# InWallDimmeSMD.net
KiCad netlist of a schematic drawn in EAGLE
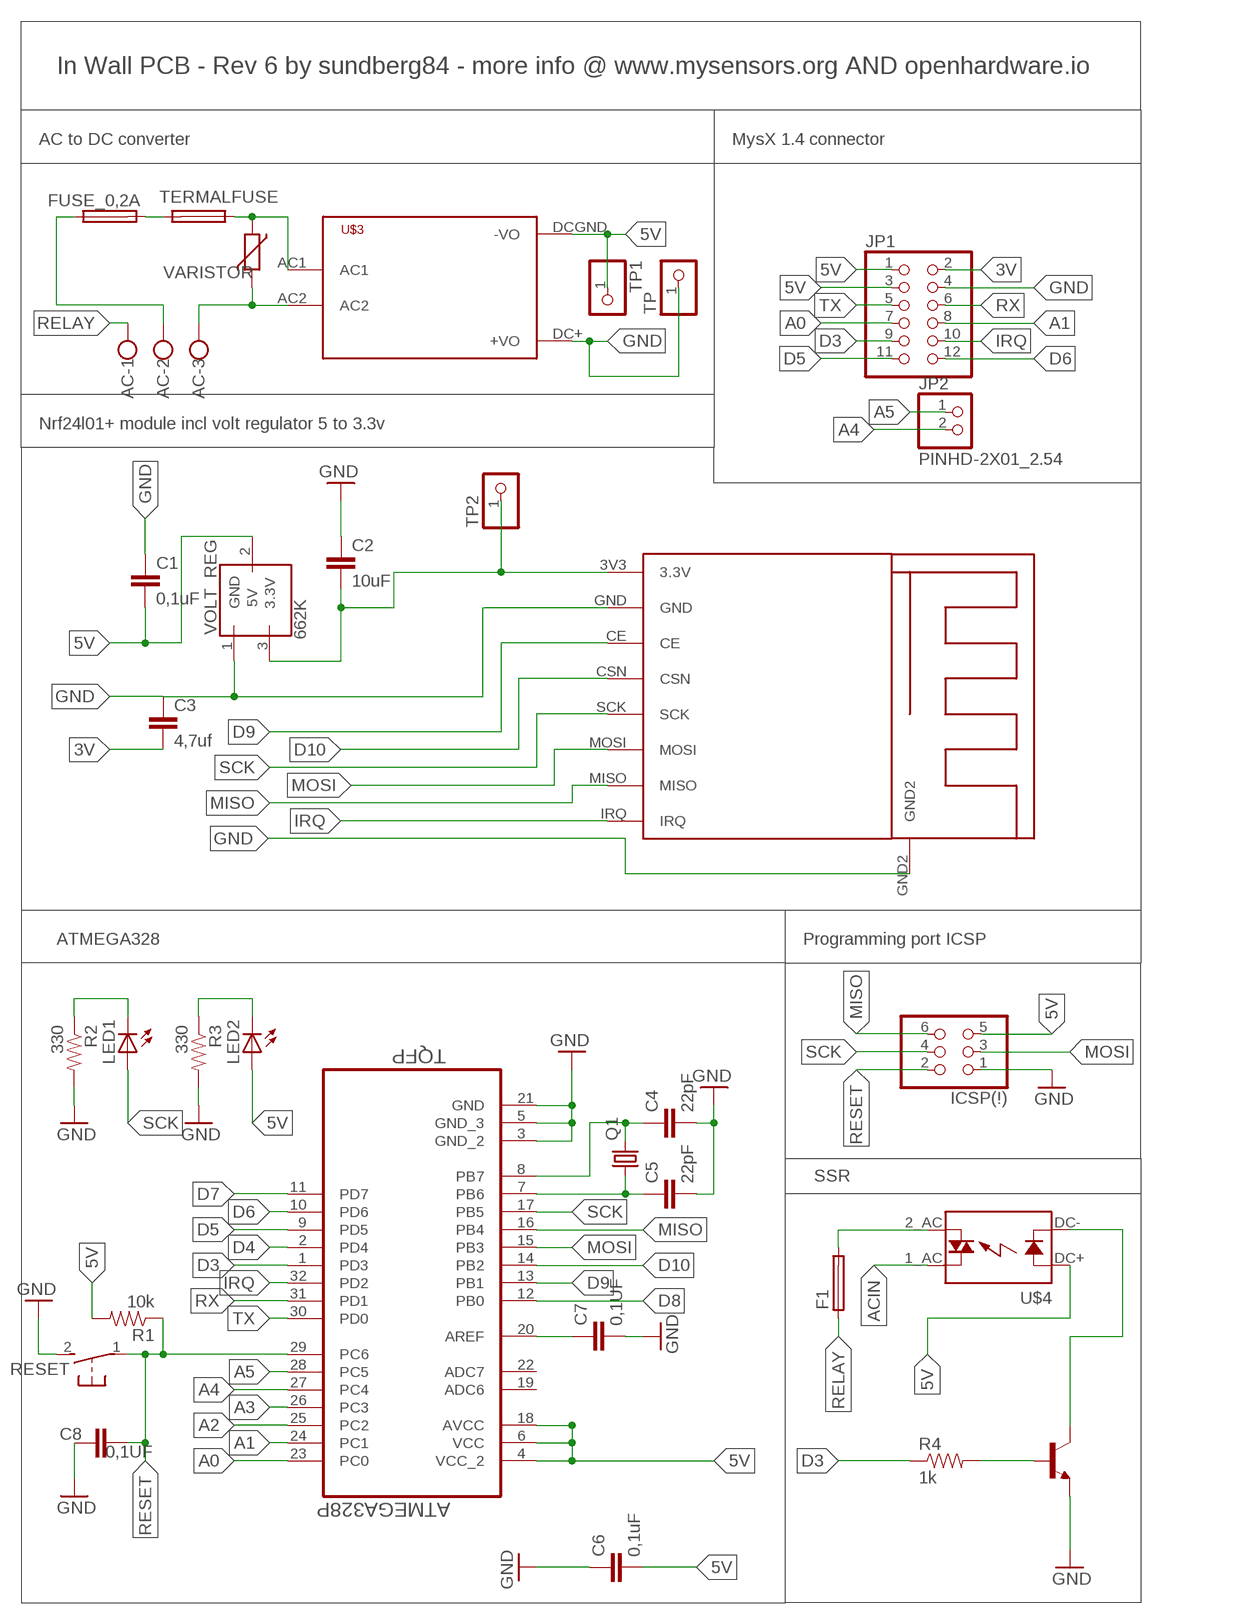
[diagram p0: schematic, sheet 1]

(export (version "E")
  (design (tool "Eeschema 10.0.6"))
  (components
    (comp (ref "AC")
      (value "W237-103")
      (footprint "eagle-import:W237-103")
      (fields (field (name "MPN") "237-103"))
      (libsource (lib "eagle-import") (part "W237-103"))
    )
    (comp (ref "ATMEGA328")
      (value "ATMEGA328P-AU")
      (footprint "eagle-import:QFP80P900X900X120-32N")
      (libsource (lib "eagle-import") (part "ATMEGA328P-AU"))
    )
    (comp (ref "C1")
      (value "0,1uF")
      (footprint "eagle-import:0805")
      (libsource (lib "eagle-import") (part "CAP0805"))
    )
    (comp (ref "C2")
      (value "10uF")
      (footprint "eagle-import:0805")
      (libsource (lib "eagle-import") (part "CAP0805"))
    )
    (comp (ref "C3")
      (value "4,7uf")
      (footprint "eagle-import:0805")
      (libsource (lib "eagle-import") (part "CAP0805"))
    )
    (comp (ref "C4")
      (value "22pF")
      (footprint "eagle-import:0805")
      (libsource (lib "eagle-import") (part "CAP0805"))
    )
    (comp (ref "C5")
      (value "22pF")
      (footprint "eagle-import:0805")
      (libsource (lib "eagle-import") (part "CAP0805"))
    )
    (comp (ref "C6")
      (value "0,1uF")
      (footprint "eagle-import:0805")
      (libsource (lib "eagle-import") (part "CAP0805"))
    )
    (comp (ref "C7")
      (value "0,1UF")
      (footprint "eagle-import:0805")
      (libsource (lib "eagle-import") (part "CAP0805"))
    )
    (comp (ref "C8")
      (value "0,1UF")
      (footprint "eagle-import:0805")
      (libsource (lib "eagle-import") (part "CAP0805"))
    )
    (comp (ref "F1")
      (value "19559")
      (footprint "eagle-import:19559")
      (fields (field (name "MPN") "55900000001"))
      (libsource (lib "eagle-import") (part "19559"))
    )
    (comp (ref "FUSE_0,2A")
      (value "FUSETE5")
      (footprint "eagle-import:TE5")
      (libsource (lib "eagle-import") (part "FUSETE5"))
    )
    (comp (ref "ICSP(!)")
      (value "PINHD-2X03_2.54")
      (footprint "eagle-import:2X03")
      (libsource (lib "eagle-import") (part "PINHD-2X03_2.54"))
    )
    (comp (ref "J3Y")
      (value "J3Y_S8050_SMD_NPN_TRANSISTOR")
      (footprint "eagle-import:SOT-23-3")
      (libsource (lib "eagle-import") (part "J3Y_S8050_SMD_NPN_TRANSISTOR"))
    )
    (comp (ref "JP1")
      (value "PINHD-2X06_2.54")
      (footprint "eagle-import:2X06")
      (libsource (lib "eagle-import") (part "PINHD-2X06_2.54"))
    )
    (comp (ref "JP2")
      (value "PINHD-2X01_2.54")
      (footprint "eagle-import:2X01")
      (libsource (lib "eagle-import") (part "PINHD-2X01_2.54"))
    )
    (comp (ref "LED1")
      (value "LEDCHIPLED_0805")
      (footprint "eagle-import:CHIPLED_0805")
      (libsource (lib "eagle-import") (part "LEDCHIPLED_0805"))
    )
    (comp (ref "LED2")
      (value "LEDCHIPLED_0805")
      (footprint "eagle-import:CHIPLED_0805")
      (libsource (lib "eagle-import") (part "LEDCHIPLED_0805"))
    )
    (comp (ref "Q1")
      (value "CRYSTALHC49S")
      (footprint "eagle-import:HC49_S")
      (libsource (lib "eagle-import") (part "CRYSTALHC49S"))
    )
    (comp (ref "R1")
      (value "10k")
      (footprint "eagle-import:0805")
      (libsource (lib "eagle-import") (part "RESISTOR0805-RES"))
    )
    (comp (ref "R2")
      (value "330")
      (footprint "eagle-import:0805")
      (libsource (lib "eagle-import") (part "RESISTOR0805-RES"))
    )
    (comp (ref "R3")
      (value "330")
      (footprint "eagle-import:0805")
      (libsource (lib "eagle-import") (part "RESISTOR0805-RES"))
    )
    (comp (ref "R4")
      (value "1k")
      (footprint "eagle-import:0805")
      (libsource (lib "eagle-import") (part "RESISTOR0805-RES"))
    )
    (comp (ref "RESET")
      (value "DTSM-3")
      (footprint "eagle-import:DTSM-3")
      (libsource (lib "eagle-import") (part "DTSM-3"))
    )
    (comp (ref "TERMALFUSE")
      (value "FUSETE5")
      (footprint "eagle-import:TE5")
      (libsource (lib "eagle-import") (part "FUSETE5"))
    )
    (comp (ref "TP")
      (value "PINHD-1X1")
      (footprint "eagle-import:1X01")
      (libsource (lib "eagle-import") (part "PINHD-1X1"))
    )
    (comp (ref "TP1")
      (value "PINHD-1X1")
      (footprint "eagle-import:1X01")
      (libsource (lib "eagle-import") (part "PINHD-1X1"))
    )
    (comp (ref "TP2")
      (value "PINHD-1X1")
      (footprint "eagle-import:1X01")
      (libsource (lib "eagle-import") (part "PINHD-1X1"))
    )
    (comp (ref "U$1")
      (value "SMD24L01+SMD")
      (footprint "eagle-import:NRF24L01+SMD")
      (libsource (lib "eagle-import") (part "SMD24L01+SMD"))
    )
    (comp (ref "U$3")
      (value "HLK-PM01")
      (footprint "eagle-import:HLK-PM01")
      (libsource (lib "eagle-import") (part "HLK-PM01"))
    )
    (comp (ref "U$4")
      (value "OMRON_G3MC-202PL_5V_SSR")
      (footprint "eagle-import:OMRON_G3MC_202PL_5V_SSR")
      (libsource (lib "eagle-import") (part "OMRON_G3MC-202PL_5V_SSR"))
    )
    (comp (ref "VARISTOR")
      (value "VARISTOR-7,5")
      (footprint "eagle-import:R-7,5")
      (libsource (lib "eagle-import") (part "VARISTOR-7,5"))
    )
    (comp (ref "VOLT_REG")
      (value "662K")
      (footprint "eagle-import:SOT-23-3")
      (libsource (lib "eagle-import") (part "662K"))
    )
  )
  (nets
    (net (code "1") (name "3V") (class "Default")
      (node (ref "C2") (pin "2") (pinfunction "2_2") (pintype "passive"))
      (node (ref "C3") (pin "2") (pinfunction "2_2") (pintype "passive"))
      (node (ref "JP1") (pin "2") (pinfunction "2_2") (pintype "passive"))
      (node (ref "TP2") (pin "1") (pinfunction "1_1") (pintype "passive"))
      (node (ref "U$1") (pin "3V3") (pinfunction "3.3V_3V3") (pintype "bidirectional"))
      (node (ref "VOLT_REG") (pin "3") (pinfunction "3.3V_3") (pintype "bidirectional"))
    )
    (net (code "2") (name "5V") (class "Default")
      (node (ref "ATMEGA328") (pin "18") (pinfunction "AVCC_18") (pintype "power_in"))
      (node (ref "ATMEGA328") (pin "4") (pinfunction "VCC_2_4") (pintype "power_in"))
      (node (ref "ATMEGA328") (pin "6") (pinfunction "VCC_6") (pintype "power_in"))
      (node (ref "C1") (pin "2") (pinfunction "2_2") (pintype "passive"))
      (node (ref "C6") (pin "2") (pinfunction "2_2") (pintype "passive"))
      (node (ref "ICSP(!)") (pin "5") (pinfunction "5_5") (pintype "passive"))
      (node (ref "JP1") (pin "1") (pinfunction "1_1") (pintype "passive"))
      (node (ref "JP1") (pin "3") (pinfunction "3_3") (pintype "passive"))
      (node (ref "LED2") (pin "A") (pinfunction "A_A") (pintype "passive"))
      (node (ref "R1") (pin "2") (pinfunction "2_2") (pintype "passive"))
      (node (ref "TP1") (pin "1") (pinfunction "1_1") (pintype "passive"))
      (node (ref "U$3") (pin "DCGND") (pinfunction "-VO_DCGND") (pintype "bidirectional"))
      (node (ref "U$4") (pin "DC+") (pinfunction "DCSIGNAL_DC+") (pintype "passive"))
      (node (ref "VOLT_REG") (pin "2") (pinfunction "5V_2") (pintype "bidirectional"))
    )
    (net (code "3") (name "A0") (class "Default")
      (node (ref "ATMEGA328") (pin "23") (pinfunction "PC0_23") (pintype "bidirectional"))
      (node (ref "JP1") (pin "7") (pinfunction "7_7") (pintype "passive"))
    )
    (net (code "4") (name "A1") (class "Default")
      (node (ref "ATMEGA328") (pin "24") (pinfunction "PC1_24") (pintype "bidirectional"))
      (node (ref "JP1") (pin "8") (pinfunction "8_8") (pintype "passive"))
    )
    (net (code "5") (name "A2") (class "Default")
      (node (ref "ATMEGA328") (pin "25") (pinfunction "PC2_25") (pintype "bidirectional"))
    )
    (net (code "6") (name "A3") (class "Default")
      (node (ref "ATMEGA328") (pin "26") (pinfunction "PC3_26") (pintype "bidirectional"))
    )
    (net (code "7") (name "A4") (class "Default")
      (node (ref "ATMEGA328") (pin "27") (pinfunction "PC4_27") (pintype "bidirectional"))
      (node (ref "JP2") (pin "2") (pinfunction "2_2") (pintype "passive"))
    )
    (net (code "8") (name "A5") (class "Default")
      (node (ref "ATMEGA328") (pin "28") (pinfunction "PC5_28") (pintype "bidirectional"))
      (node (ref "JP2") (pin "1") (pinfunction "1_1") (pintype "passive"))
    )
    (net (code "9") (name "ACIN") (class "Default")
      (node (ref "AC") (pin "2") (pinfunction "KL_2") (pintype "passive"))
      (node (ref "FUSE_0,2A") (pin "1") (pinfunction "1_1") (pintype "passive"))
      (node (ref "U$4") (pin "1_AC") (pinfunction "HOT_1_AC") (pintype "passive"))
    )
    (net (code "10") (name "D3") (class "Default")
      (node (ref "ATMEGA328") (pin "1") (pinfunction "PD3_1") (pintype "bidirectional"))
      (node (ref "JP1") (pin "9") (pinfunction "9_9") (pintype "passive"))
      (node (ref "R4") (pin "1") (pinfunction "1_1") (pintype "passive"))
    )
    (net (code "11") (name "D4") (class "Default")
      (node (ref "ATMEGA328") (pin "2") (pinfunction "PD4_2") (pintype "bidirectional"))
    )
    (net (code "12") (name "D5") (class "Default")
      (node (ref "ATMEGA328") (pin "9") (pinfunction "PD5_9") (pintype "bidirectional"))
      (node (ref "JP1") (pin "11") (pinfunction "11_11") (pintype "passive"))
    )
    (net (code "13") (name "D6") (class "Default")
      (node (ref "ATMEGA328") (pin "10") (pinfunction "PD6_10") (pintype "bidirectional"))
      (node (ref "JP1") (pin "12") (pinfunction "12_12") (pintype "passive"))
    )
    (net (code "14") (name "D7") (class "Default")
      (node (ref "ATMEGA328") (pin "11") (pinfunction "PD7_11") (pintype "bidirectional"))
    )
    (net (code "15") (name "D8") (class "Default")
      (node (ref "ATMEGA328") (pin "12") (pinfunction "PB0_12") (pintype "bidirectional"))
    )
    (net (code "16") (name "D9") (class "Default")
      (node (ref "ATMEGA328") (pin "13") (pinfunction "PB1_13") (pintype "bidirectional"))
      (node (ref "U$1") (pin "CE") (pinfunction "CE_CE") (pintype "bidirectional"))
    )
    (net (code "17") (name "D10") (class "Default")
      (node (ref "ATMEGA328") (pin "14") (pinfunction "PB2_14") (pintype "bidirectional"))
      (node (ref "U$1") (pin "CSN") (pinfunction "CSN_CSN") (pintype "bidirectional"))
    )
    (net (code "18") (name "GND") (class "Default")
      (node (ref "ATMEGA328") (pin "21") (pinfunction "GND_21") (pintype "passive"))
      (node (ref "ATMEGA328") (pin "3") (pinfunction "GND_2_3") (pintype "passive"))
      (node (ref "ATMEGA328") (pin "5") (pinfunction "GND_3_5") (pintype "passive"))
      (node (ref "C1") (pin "1") (pinfunction "1_1") (pintype "passive"))
      (node (ref "C2") (pin "1") (pinfunction "1_1") (pintype "passive"))
      (node (ref "C3") (pin "1") (pinfunction "1_1") (pintype "passive"))
      (node (ref "C4") (pin "2") (pinfunction "2_2") (pintype "passive"))
      (node (ref "C5") (pin "2") (pinfunction "2_2") (pintype "passive"))
      (node (ref "C6") (pin "1") (pinfunction "1_1") (pintype "passive"))
      (node (ref "C7") (pin "2") (pinfunction "2_2") (pintype "passive"))
      (node (ref "C8") (pin "1") (pinfunction "1_1") (pintype "passive"))
      (node (ref "ICSP(!)") (pin "1") (pinfunction "1_1") (pintype "passive"))
      (node (ref "J3Y") (pin "3") (pinfunction "E_3") (pintype "passive"))
      (node (ref "JP1") (pin "4") (pinfunction "4_4") (pintype "passive"))
      (node (ref "R2") (pin "2") (pinfunction "2_2") (pintype "passive"))
      (node (ref "R3") (pin "2") (pinfunction "2_2") (pintype "passive"))
      (node (ref "RESET") (pin "2") (pinfunction "2_2") (pintype "passive"))
      (node (ref "TP") (pin "1") (pinfunction "1_1") (pintype "passive"))
      (node (ref "U$1") (pin "GND") (pinfunction "GND_GND") (pintype "bidirectional"))
      (node (ref "U$1") (pin "GND2") (pinfunction "GND2_GND2") (pintype "bidirectional"))
      (node (ref "U$3") (pin "DC+") (pinfunction "+VO_DC+") (pintype "bidirectional"))
      (node (ref "VOLT_REG") (pin "1") (pinfunction "GND_1") (pintype "bidirectional"))
    )
    (net (code "19") (name "IRQ") (class "Default")
      (node (ref "ATMEGA328") (pin "32") (pinfunction "PD2_32") (pintype "bidirectional"))
      (node (ref "JP1") (pin "10") (pinfunction "10_10") (pintype "passive"))
      (node (ref "U$1") (pin "IRQ") (pinfunction "IRQ_IRQ") (pintype "bidirectional"))
    )
    (net (code "20") (name "MISO") (class "Default")
      (node (ref "ATMEGA328") (pin "16") (pinfunction "PB4_16") (pintype "bidirectional"))
      (node (ref "ICSP(!)") (pin "6") (pinfunction "6_6") (pintype "passive"))
      (node (ref "U$1") (pin "MISO") (pinfunction "MISO_MISO") (pintype "bidirectional"))
    )
    (net (code "21") (name "MOSI") (class "Default")
      (node (ref "ATMEGA328") (pin "15") (pinfunction "PB3_15") (pintype "bidirectional"))
      (node (ref "ICSP(!)") (pin "3") (pinfunction "3_3") (pintype "passive"))
      (node (ref "U$1") (pin "MOSI") (pinfunction "MOSI_MOSI") (pintype "bidirectional"))
    )
    (net (code "22") (name "Net-(ACC-KL)") (class "Default")
      (node (ref "AC") (pin "3") (pinfunction "KL_3") (pintype "passive"))
      (node (ref "U$3") (pin "AC2") (pinfunction "AC2_AC2") (pintype "bidirectional"))
      (node (ref "VARISTOR") (pin "2") (pinfunction "2_2") (pintype "passive"))
    )
    (net (code "23") (name "Net-(ATMEGA328-AREF)") (class "Default")
      (node (ref "ATMEGA328") (pin "20") (pinfunction "AREF_20") (pintype "input"))
      (node (ref "C7") (pin "1") (pinfunction "1_1") (pintype "passive"))
    )
    (net (code "24") (name "Net-(ATMEGA328-PB6)") (class "Default")
      (node (ref "ATMEGA328") (pin "7") (pinfunction "PB6_7") (pintype "bidirectional"))
      (node (ref "C5") (pin "1") (pinfunction "1_1") (pintype "passive"))
      (node (ref "Q1") (pin "1") (pinfunction "1_1") (pintype "passive"))
    )
    (net (code "25") (name "Net-(ATMEGA328-PB7)") (class "Default")
      (node (ref "ATMEGA328") (pin "8") (pinfunction "PB7_8") (pintype "bidirectional"))
      (node (ref "C4") (pin "1") (pinfunction "1_1") (pintype "passive"))
      (node (ref "Q1") (pin "2") (pinfunction "2_2") (pintype "passive"))
    )
    (net (code "26") (name "Net-(FUSE_0,2A-Pad2)") (class "Default")
      (node (ref "FUSE_0,2A") (pin "2") (pinfunction "2_2") (pintype "passive"))
      (node (ref "TERMALFUSE") (pin "2") (pinfunction "2_2") (pintype "passive"))
    )
    (net (code "27") (name "Net-(J3Y-B)") (class "Default")
      (node (ref "J3Y") (pin "1") (pinfunction "B_1") (pintype "passive"))
      (node (ref "R4") (pin "2") (pinfunction "2_2") (pintype "passive"))
    )
    (net (code "28") (name "Net-(J3Y-C)") (class "Default")
      (node (ref "J3Y") (pin "2") (pinfunction "C_2") (pintype "passive"))
      (node (ref "U$4") (pin "DC-") (pinfunction "DCGND_DC-") (pintype "passive"))
    )
    (net (code "29") (name "Net-(LED1-PadC)") (class "Default")
      (node (ref "LED1") (pin "C") (pinfunction "C_C") (pintype "passive"))
      (node (ref "R2") (pin "1") (pinfunction "1_1") (pintype "passive"))
    )
    (net (code "30") (name "Net-(LED2-PadC)") (class "Default")
      (node (ref "LED2") (pin "C") (pinfunction "C_C") (pintype "passive"))
      (node (ref "R3") (pin "1") (pinfunction "1_1") (pintype "passive"))
    )
    (net (code "31") (name "Net-(TERMALFUSE-Pad1)") (class "Default")
      (node (ref "TERMALFUSE") (pin "1") (pinfunction "1_1") (pintype "passive"))
      (node (ref "U$3") (pin "AC1") (pinfunction "AC1_AC1") (pintype "bidirectional"))
      (node (ref "VARISTOR") (pin "1") (pinfunction "1_1") (pintype "passive"))
    )
    (net (code "32") (name "Net-(U$4-NEUTRAL)") (class "Default")
      (node (ref "F1") (pin "2") (pinfunction "2_2") (pintype "passive"))
      (node (ref "U$4") (pin "2_AC") (pinfunction "NEUTRAL_2_AC") (pintype "passive"))
    )
    (net (code "33") (name "RELAY") (class "Default")
      (node (ref "AC") (pin "1") (pinfunction "KL_1") (pintype "passive"))
      (node (ref "F1") (pin "1") (pinfunction "1_1") (pintype "passive"))
    )
    (net (code "34") (name "RESET") (class "Default")
      (node (ref "ATMEGA328") (pin "29") (pinfunction "PC6_29") (pintype "bidirectional"))
      (node (ref "C8") (pin "2") (pinfunction "2_2") (pintype "passive"))
      (node (ref "ICSP(!)") (pin "2") (pinfunction "2_2") (pintype "passive"))
      (node (ref "R1") (pin "1") (pinfunction "1_1") (pintype "passive"))
      (node (ref "RESET") (pin "1") (pinfunction "1_1") (pintype "passive"))
    )
    (net (code "35") (name "RX") (class "Default")
      (node (ref "ATMEGA328") (pin "31") (pinfunction "PD1_31") (pintype "bidirectional"))
      (node (ref "JP1") (pin "6") (pinfunction "6_6") (pintype "passive"))
    )
    (net (code "36") (name "SCK") (class "Default")
      (node (ref "ATMEGA328") (pin "17") (pinfunction "PB5_17") (pintype "bidirectional"))
      (node (ref "ICSP(!)") (pin "4") (pinfunction "4_4") (pintype "passive"))
      (node (ref "LED1") (pin "A") (pinfunction "A_A") (pintype "passive"))
      (node (ref "U$1") (pin "SCK") (pinfunction "SCK_SCK") (pintype "bidirectional"))
    )
    (net (code "37") (name "TX") (class "Default")
      (node (ref "ATMEGA328") (pin "30") (pinfunction "PD0_30") (pintype "bidirectional"))
      (node (ref "JP1") (pin "5") (pinfunction "5_5") (pintype "passive"))
    )
    (net (code "38") (name "unconnected-(ATMEGA328-ADC6-Pad19)") (class "Default")
      (node (ref "ATMEGA328") (pin "19") (pinfunction "ADC6_19") (pintype "input"))
    )
    (net (code "39") (name "unconnected-(ATMEGA328-ADC7-Pad22)") (class "Default")
      (node (ref "ATMEGA328") (pin "22") (pinfunction "ADC7_22") (pintype "input"))
    )
  )
)
